# carte.net
KiCad netlist of a schematic drawn in EAGLE
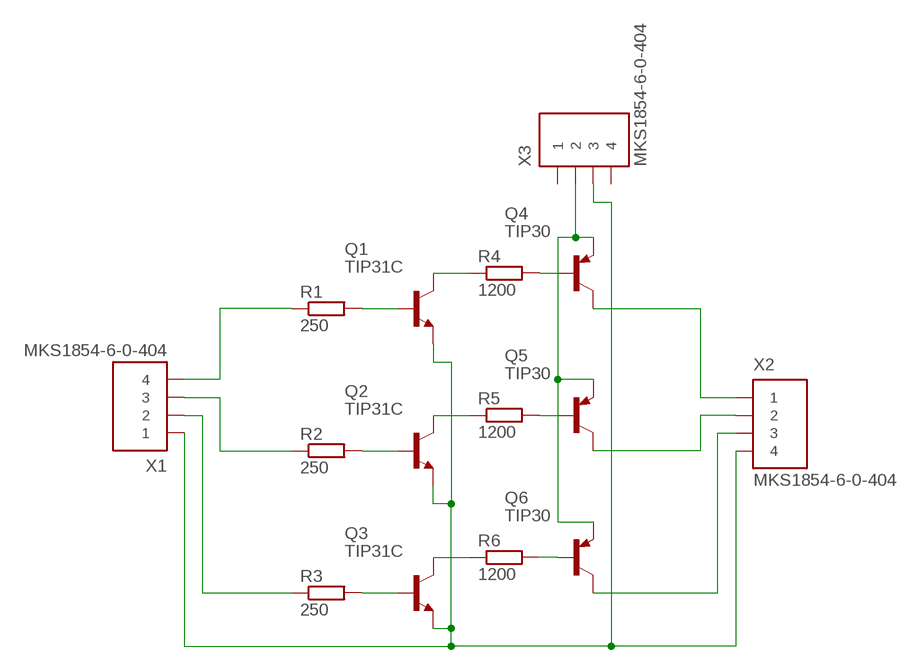
[diagram p0: schematic, sheet 1]

(export (version "E")
  (design (tool "Eeschema 10.0.6"))
  (components
    (comp (ref "Q1")
      (value "TIP31C")
      (footprint "eagle-import:TO220")
      (libsource (lib "eagle-import") (part "TIP31C"))
    )
    (comp (ref "Q2")
      (value "TIP31C")
      (footprint "eagle-import:TO220")
      (libsource (lib "eagle-import") (part "TIP31C"))
    )
    (comp (ref "Q3")
      (value "TIP31C")
      (footprint "eagle-import:TO220")
      (libsource (lib "eagle-import") (part "TIP31C"))
    )
    (comp (ref "Q4")
      (value "TIP30")
      (footprint "eagle-import:TO220")
      (libsource (lib "eagle-import") (part "TIP30"))
    )
    (comp (ref "Q5")
      (value "TIP30")
      (footprint "eagle-import:TO220")
      (libsource (lib "eagle-import") (part "TIP30"))
    )
    (comp (ref "Q6")
      (value "TIP30")
      (footprint "eagle-import:TO220")
      (libsource (lib "eagle-import") (part "TIP30"))
    )
    (comp (ref "R1")
      (value "250")
      (footprint "eagle-import:0207_10")
      (libsource (lib "eagle-import") (part "R-EU_0207/10"))
    )
    (comp (ref "R2")
      (value "250")
      (footprint "eagle-import:0207_10")
      (libsource (lib "eagle-import") (part "R-EU_0207/10"))
    )
    (comp (ref "R3")
      (value "250")
      (footprint "eagle-import:0207_10")
      (libsource (lib "eagle-import") (part "R-EU_0207/10"))
    )
    (comp (ref "R4")
      (value "1200")
      (footprint "eagle-import:0207_10")
      (libsource (lib "eagle-import") (part "R-EU_0207/10"))
    )
    (comp (ref "R5")
      (value "1200")
      (footprint "eagle-import:0207_10")
      (libsource (lib "eagle-import") (part "R-EU_0207/10"))
    )
    (comp (ref "R6")
      (value "1200")
      (footprint "eagle-import:0207_10")
      (libsource (lib "eagle-import") (part "R-EU_0207/10"))
    )
    (comp (ref "X1")
      (value "MKS1854-6-0-404")
      (footprint "eagle-import:MKS1854-6-0-404")
      (libsource (lib "eagle-import") (part "MKS1854-6-0-404"))
    )
    (comp (ref "X2")
      (value "MKS1854-6-0-404")
      (footprint "eagle-import:MKS1854-6-0-404")
      (libsource (lib "eagle-import") (part "MKS1854-6-0-404"))
    )
    (comp (ref "X3")
      (value "MKS1854-6-0-404")
      (footprint "eagle-import:MKS1854-6-0-404")
      (libsource (lib "eagle-import") (part "MKS1854-6-0-404"))
    )
  )
  (nets
    (net (code "1") (name "Net-(Q1-B)") (class "Default")
      (node (ref "Q1") (pin "1") (pinfunction "B_1") (pintype "passive"))
      (node (ref "R1") (pin "2") (pinfunction "2_2") (pintype "passive"))
    )
    (net (code "2") (name "Net-(Q1-C)") (class "Default")
      (node (ref "Q1") (pin "2") (pinfunction "C_2") (pintype "passive"))
      (node (ref "R4") (pin "1") (pinfunction "1_1") (pintype "passive"))
    )
    (net (code "3") (name "Net-(Q1-E)") (class "Default")
      (node (ref "Q1") (pin "3") (pinfunction "E_3") (pintype "passive"))
      (node (ref "Q2") (pin "3") (pinfunction "E_3") (pintype "passive"))
      (node (ref "Q3") (pin "3") (pinfunction "E_3") (pintype "passive"))
      (node (ref "X1") (pin "1") (pinfunction "1_1") (pintype "input"))
      (node (ref "X2") (pin "4") (pinfunction "4_4") (pintype "input"))
      (node (ref "X3") (pin "3") (pinfunction "3_3") (pintype "input"))
    )
    (net (code "4") (name "Net-(Q2-B)") (class "Default")
      (node (ref "Q2") (pin "1") (pinfunction "B_1") (pintype "passive"))
      (node (ref "R2") (pin "2") (pinfunction "2_2") (pintype "passive"))
    )
    (net (code "5") (name "Net-(Q2-C)") (class "Default")
      (node (ref "Q2") (pin "2") (pinfunction "C_2") (pintype "passive"))
      (node (ref "R5") (pin "1") (pinfunction "1_1") (pintype "passive"))
    )
    (net (code "6") (name "Net-(Q3-B)") (class "Default")
      (node (ref "Q3") (pin "1") (pinfunction "B_1") (pintype "passive"))
      (node (ref "R3") (pin "2") (pinfunction "2_2") (pintype "passive"))
    )
    (net (code "7") (name "Net-(Q3-C)") (class "Default")
      (node (ref "Q3") (pin "2") (pinfunction "C_2") (pintype "passive"))
      (node (ref "R6") (pin "1") (pinfunction "1_1") (pintype "passive"))
    )
    (net (code "8") (name "Net-(Q4-B)") (class "Default")
      (node (ref "Q4") (pin "1") (pinfunction "B_1") (pintype "passive"))
      (node (ref "R4") (pin "2") (pinfunction "2_2") (pintype "passive"))
    )
    (net (code "9") (name "Net-(Q4-C)") (class "Default")
      (node (ref "Q4") (pin "2") (pinfunction "C_2") (pintype "passive"))
      (node (ref "X2") (pin "1") (pinfunction "1_1") (pintype "input"))
    )
    (net (code "10") (name "Net-(Q4-E)") (class "Default")
      (node (ref "Q4") (pin "3") (pinfunction "E_3") (pintype "passive"))
      (node (ref "Q5") (pin "3") (pinfunction "E_3") (pintype "passive"))
      (node (ref "Q6") (pin "3") (pinfunction "E_3") (pintype "passive"))
      (node (ref "X3") (pin "2") (pinfunction "2_2") (pintype "input"))
    )
    (net (code "11") (name "Net-(Q5-B)") (class "Default")
      (node (ref "Q5") (pin "1") (pinfunction "B_1") (pintype "passive"))
      (node (ref "R5") (pin "2") (pinfunction "2_2") (pintype "passive"))
    )
    (net (code "12") (name "Net-(Q5-C)") (class "Default")
      (node (ref "Q5") (pin "2") (pinfunction "C_2") (pintype "passive"))
      (node (ref "X2") (pin "2") (pinfunction "2_2") (pintype "input"))
    )
    (net (code "13") (name "Net-(Q6-B)") (class "Default")
      (node (ref "Q6") (pin "1") (pinfunction "B_1") (pintype "passive"))
      (node (ref "R6") (pin "2") (pinfunction "2_2") (pintype "passive"))
    )
    (net (code "14") (name "Net-(Q6-C)") (class "Default")
      (node (ref "Q6") (pin "2") (pinfunction "C_2") (pintype "passive"))
      (node (ref "X2") (pin "3") (pinfunction "3_3") (pintype "input"))
    )
    (net (code "15") (name "Net-(R1-Pad1)") (class "Default")
      (node (ref "R1") (pin "1") (pinfunction "1_1") (pintype "passive"))
      (node (ref "X1") (pin "4") (pinfunction "4_4") (pintype "input"))
    )
    (net (code "16") (name "Net-(R2-Pad1)") (class "Default")
      (node (ref "R2") (pin "1") (pinfunction "1_1") (pintype "passive"))
      (node (ref "X1") (pin "3") (pinfunction "3_3") (pintype "input"))
    )
    (net (code "17") (name "Net-(R3-Pad1)") (class "Default")
      (node (ref "R3") (pin "1") (pinfunction "1_1") (pintype "passive"))
      (node (ref "X1") (pin "2") (pinfunction "2_2") (pintype "input"))
    )
    (net (code "18") (name "unconnected-(X3-Pad1)") (class "Default")
      (node (ref "X3") (pin "1") (pinfunction "1_1") (pintype "input"))
    )
    (net (code "19") (name "unconnected-(X3-Pad4)") (class "Default")
      (node (ref "X3") (pin "4") (pinfunction "4_4") (pintype "input"))
    )
  )
)
